# LEDs3.net
KiCad netlist of a schematic drawn in EAGLE
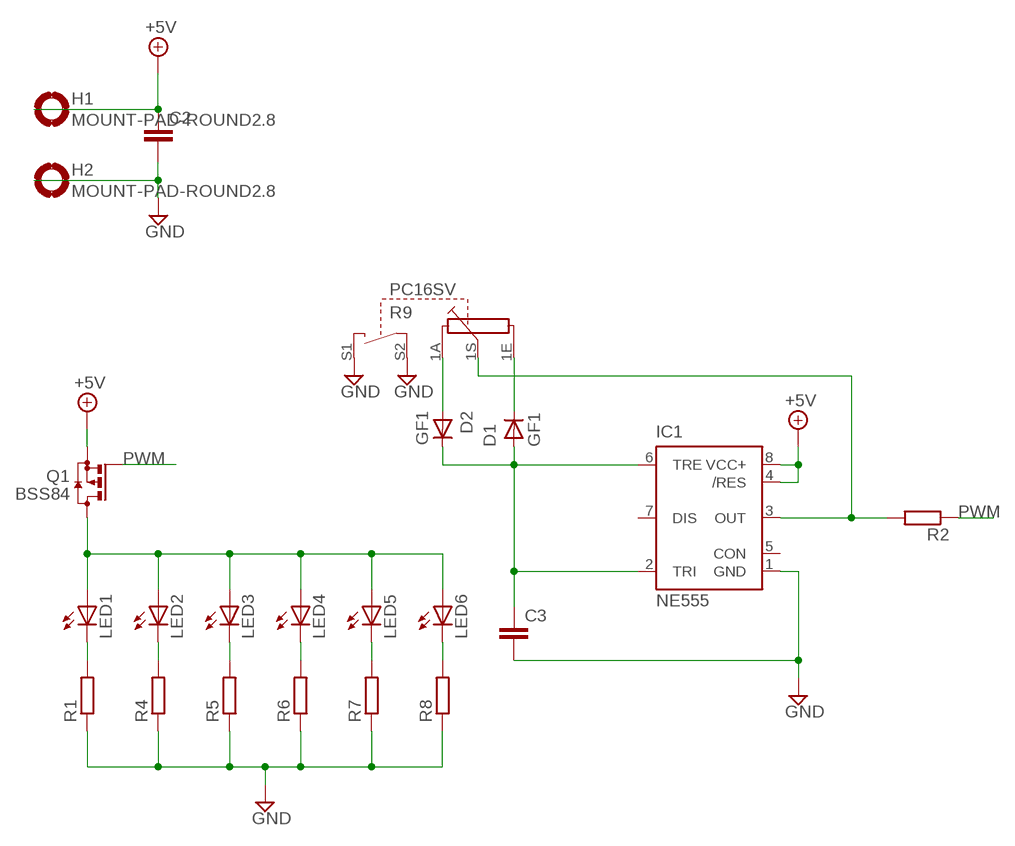
[diagram p0: schematic, sheet 1]

(export (version "E")
  (design (tool "Eeschema 10.0.6"))
  (components
    (comp (ref "C2")
      (value "C-EUC1206K")
      (footprint "eagle-import:C1206K")
      (libsource (lib "eagle-import") (part "C-EUC1206K"))
    )
    (comp (ref "C3")
      (value "C-EUC0805")
      (footprint "eagle-import:C0805")
      (libsource (lib "eagle-import") (part "C-EUC0805"))
    )
    (comp (ref "D1")
      (value "GF1")
      (footprint "eagle-import:SMA-DO214AC")
      (libsource (lib "eagle-import") (part "GF1"))
    )
    (comp (ref "D2")
      (value "GF1")
      (footprint "eagle-import:SMA-DO214AC")
      (libsource (lib "eagle-import") (part "GF1"))
    )
    (comp (ref "H1")
      (value "MOUNT-PAD-ROUND2.8")
      (footprint "eagle-import:2,8-PAD")
      (libsource (lib "eagle-import") (part "MOUNT-PAD-ROUND2.8"))
    )
    (comp (ref "H2")
      (value "MOUNT-PAD-ROUND2.8")
      (footprint "eagle-import:2,8-PAD")
      (libsource (lib "eagle-import") (part "MOUNT-PAD-ROUND2.8"))
    )
    (comp (ref "IC1")
      (value "NE555")
      (footprint "eagle-import:DIL-08")
      (fields (field (name "MF") "Arrow Electronics") (field (name "MPN") "NE555N"))
      (libsource (lib "eagle-import") (part "NE555"))
    )
    (comp (ref "LED1")
      (value "LED-2AC-CP41B-WES")
      (footprint "eagle-import:CP41B")
      (libsource (lib "eagle-import") (part "LED-2AC-CP41B-WES"))
    )
    (comp (ref "LED2")
      (value "LED-2AC-CP41B-WES")
      (footprint "eagle-import:CP41B")
      (libsource (lib "eagle-import") (part "LED-2AC-CP41B-WES"))
    )
    (comp (ref "LED3")
      (value "LED-2AC-CP41B-WES")
      (footprint "eagle-import:CP41B")
      (libsource (lib "eagle-import") (part "LED-2AC-CP41B-WES"))
    )
    (comp (ref "LED4")
      (value "LED-2AC-CP41B-WES")
      (footprint "eagle-import:CP41B")
      (libsource (lib "eagle-import") (part "LED-2AC-CP41B-WES"))
    )
    (comp (ref "LED5")
      (value "LED-2AC-CP41B-WES")
      (footprint "eagle-import:CP41B")
      (libsource (lib "eagle-import") (part "LED-2AC-CP41B-WES"))
    )
    (comp (ref "LED6")
      (value "LED-2AC-CP41B-WES")
      (footprint "eagle-import:CP41B")
      (libsource (lib "eagle-import") (part "LED-2AC-CP41B-WES"))
    )
    (comp (ref "Q1")
      (value "BSS84")
      (footprint "eagle-import:SOT23")
      (libsource (lib "eagle-import") (part "BSS84"))
    )
    (comp (ref "R1")
      (value "R-EU_M0805")
      (footprint "eagle-import:M0805")
      (libsource (lib "eagle-import") (part "R-EU_M0805"))
    )
    (comp (ref "R2")
      (value "R-EU_M0805")
      (footprint "eagle-import:M0805")
      (libsource (lib "eagle-import") (part "R-EU_M0805"))
    )
    (comp (ref "R4")
      (value "R-EU_M0805")
      (footprint "eagle-import:M0805")
      (libsource (lib "eagle-import") (part "R-EU_M0805"))
    )
    (comp (ref "R5")
      (value "R-EU_M0805")
      (footprint "eagle-import:M0805")
      (libsource (lib "eagle-import") (part "R-EU_M0805"))
    )
    (comp (ref "R6")
      (value "R-EU_M0805")
      (footprint "eagle-import:M0805")
      (libsource (lib "eagle-import") (part "R-EU_M0805"))
    )
    (comp (ref "R7")
      (value "R-EU_M0805")
      (footprint "eagle-import:M0805")
      (libsource (lib "eagle-import") (part "R-EU_M0805"))
    )
    (comp (ref "R8")
      (value "R-EU_M0805")
      (footprint "eagle-import:M0805")
      (libsource (lib "eagle-import") (part "R-EU_M0805"))
    )
    (comp (ref "R9")
      (value "PC16SV")
      (footprint "eagle-import:PC16SV")
      (libsource (lib "eagle-import") (part "PC16SV"))
    )
  )
  (nets
    (net (code "1") (name "+5V") (class "Default")
      (node (ref "C2") (pin "1") (pinfunction "1_1") (pintype "passive"))
      (node (ref "H1") (pin "B2,8") (pinfunction "MOUNT_B2,8") (pintype "passive"))
      (node (ref "IC1") (pin "4") (pinfunction "/RES_4") (pintype "input"))
      (node (ref "IC1") (pin "8") (pinfunction "VCC+_8") (pintype "power_in"))
      (node (ref "Q1") (pin "2") (pinfunction "S_2") (pintype "passive"))
    )
    (net (code "2") (name "/PWM") (class "Default")
      (node (ref "Q1") (pin "1") (pinfunction "G_1") (pintype "passive"))
      (node (ref "R2") (pin "1") (pinfunction "1_1") (pintype "passive"))
    )
    (net (code "3") (name "GND") (class "Default")
      (node (ref "C2") (pin "2") (pinfunction "2_2") (pintype "passive"))
      (node (ref "C3") (pin "2") (pinfunction "2_2") (pintype "passive"))
      (node (ref "H2") (pin "B2,8") (pinfunction "MOUNT_B2,8") (pintype "passive"))
      (node (ref "IC1") (pin "1") (pinfunction "GND_1") (pintype "power_in"))
      (node (ref "R1") (pin "1") (pinfunction "1_1") (pintype "passive"))
      (node (ref "R4") (pin "1") (pinfunction "1_1") (pintype "passive"))
      (node (ref "R5") (pin "1") (pinfunction "1_1") (pintype "passive"))
      (node (ref "R6") (pin "1") (pinfunction "1_1") (pintype "passive"))
      (node (ref "R7") (pin "1") (pinfunction "1_1") (pintype "passive"))
      (node (ref "R8") (pin "1") (pinfunction "1_1") (pintype "passive"))
      (node (ref "R9") (pin "S1") (pinfunction "S1_S1") (pintype "passive"))
      (node (ref "R9") (pin "S2") (pinfunction "S2_S2") (pintype "passive"))
    )
    (net (code "4") (name "Net-(D1-C)") (class "Default")
      (node (ref "D1") (pin "K") (pinfunction "C_K") (pintype "passive"))
      (node (ref "R9") (pin "1E") (pinfunction "1E_1E") (pintype "passive"))
    )
    (net (code "5") (name "Net-(D2-C)") (class "Default")
      (node (ref "C3") (pin "1") (pinfunction "1_1") (pintype "passive"))
      (node (ref "D1") (pin "A") (pinfunction "A_A") (pintype "passive"))
      (node (ref "D2") (pin "K") (pinfunction "C_K") (pintype "passive"))
      (node (ref "IC1") (pin "2") (pinfunction "TRI_2") (pintype "input"))
      (node (ref "IC1") (pin "6") (pinfunction "TRE_6") (pintype "input"))
    )
    (net (code "6") (name "Net-(D2-PadA)") (class "Default")
      (node (ref "D2") (pin "A") (pinfunction "A_A") (pintype "passive"))
      (node (ref "R9") (pin "1A") (pinfunction "1A_1A") (pintype "passive"))
    )
    (net (code "7") (name "Net-(IC1-OUT)") (class "Default")
      (node (ref "IC1") (pin "3") (pinfunction "OUT_3") (pintype "output"))
      (node (ref "R2") (pin "2") (pinfunction "2_2") (pintype "passive"))
      (node (ref "R9") (pin "1S") (pinfunction "1S_1S") (pintype "passive"))
    )
    (net (code "8") (name "Net-(LED1-C-Pad1)") (class "Default")
      (node (ref "LED1") (pin "1") (pinfunction "C_1") (pintype "passive"))
      (node (ref "LED1") (pin "4") (pinfunction "C_4") (pintype "passive"))
      (node (ref "R1") (pin "2") (pinfunction "2_2") (pintype "passive"))
    )
    (net (code "9") (name "Net-(LED2-C-Pad1)") (class "Default")
      (node (ref "LED2") (pin "1") (pinfunction "C_1") (pintype "passive"))
      (node (ref "LED2") (pin "4") (pinfunction "C_4") (pintype "passive"))
      (node (ref "R4") (pin "2") (pinfunction "2_2") (pintype "passive"))
    )
    (net (code "10") (name "Net-(LED3-C-Pad1)") (class "Default")
      (node (ref "LED3") (pin "1") (pinfunction "C_1") (pintype "passive"))
      (node (ref "LED3") (pin "4") (pinfunction "C_4") (pintype "passive"))
      (node (ref "R5") (pin "2") (pinfunction "2_2") (pintype "passive"))
    )
    (net (code "11") (name "Net-(LED4-C-Pad1)") (class "Default")
      (node (ref "LED4") (pin "1") (pinfunction "C_1") (pintype "passive"))
      (node (ref "LED4") (pin "4") (pinfunction "C_4") (pintype "passive"))
      (node (ref "R6") (pin "2") (pinfunction "2_2") (pintype "passive"))
    )
    (net (code "12") (name "Net-(LED5-C-Pad1)") (class "Default")
      (node (ref "LED5") (pin "1") (pinfunction "C_1") (pintype "passive"))
      (node (ref "LED5") (pin "4") (pinfunction "C_4") (pintype "passive"))
      (node (ref "R7") (pin "2") (pinfunction "2_2") (pintype "passive"))
    )
    (net (code "13") (name "Net-(LED6-C-Pad1)") (class "Default")
      (node (ref "LED6") (pin "1") (pinfunction "C_1") (pintype "passive"))
      (node (ref "LED6") (pin "4") (pinfunction "C_4") (pintype "passive"))
      (node (ref "R8") (pin "2") (pinfunction "2_2") (pintype "passive"))
    )
    (net (code "14") (name "Net-(Q1-D)") (class "Default")
      (node (ref "LED1") (pin "2") (pinfunction "A_2") (pintype "passive"))
      (node (ref "LED1") (pin "3") (pinfunction "A_3") (pintype "passive"))
      (node (ref "LED2") (pin "2") (pinfunction "A_2") (pintype "passive"))
      (node (ref "LED2") (pin "3") (pinfunction "A_3") (pintype "passive"))
      (node (ref "LED3") (pin "2") (pinfunction "A_2") (pintype "passive"))
      (node (ref "LED3") (pin "3") (pinfunction "A_3") (pintype "passive"))
      (node (ref "LED4") (pin "2") (pinfunction "A_2") (pintype "passive"))
      (node (ref "LED4") (pin "3") (pinfunction "A_3") (pintype "passive"))
      (node (ref "LED5") (pin "2") (pinfunction "A_2") (pintype "passive"))
      (node (ref "LED5") (pin "3") (pinfunction "A_3") (pintype "passive"))
      (node (ref "LED6") (pin "2") (pinfunction "A_2") (pintype "passive"))
      (node (ref "LED6") (pin "3") (pinfunction "A_3") (pintype "passive"))
      (node (ref "Q1") (pin "3") (pinfunction "D_3") (pintype "passive"))
    )
    (net (code "15") (name "unconnected-(IC1-CON-Pad5)") (class "Default")
      (node (ref "IC1") (pin "5") (pinfunction "CON_5") (pintype "input"))
    )
    (net (code "16") (name "unconnected-(IC1-DIS-Pad7)") (class "Default")
      (node (ref "IC1") (pin "7") (pinfunction "DIS_7") (pintype "input"))
    )
  )
)
